# Power.net
KiCad netlist of a schematic drawn in Altium Designer
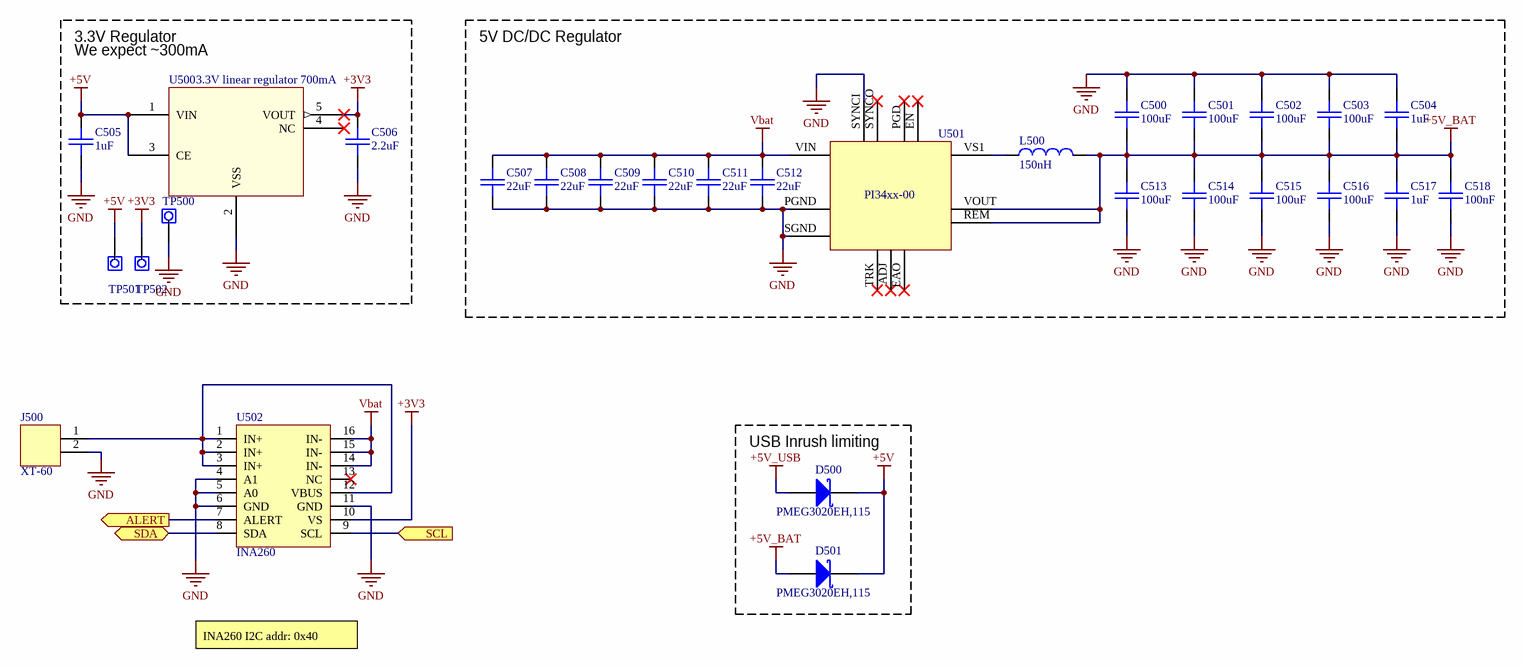
[diagram p0: Power.SchDoc]

(export (version "E")
  (design (tool "Eeschema 10.0.6"))
  (components
    (comp (ref "C500")
      (value "100uF")
      (footprint "1206_CAP")
      (libsource (lib "Moonlight-Components") (part "Capacitor"))
    )
    (comp (ref "C501")
      (value "100uF")
      (footprint "1206_CAP")
      (libsource (lib "Moonlight-Components") (part "Capacitor"))
    )
    (comp (ref "C502")
      (value "100uF")
      (footprint "1206_CAP")
      (libsource (lib "Moonlight-Components") (part "Capacitor"))
    )
    (comp (ref "C503")
      (value "100uF")
      (footprint "1206_CAP")
      (libsource (lib "Moonlight-Components") (part "Capacitor"))
    )
    (comp (ref "C504")
      (value "1uF")
      (footprint "0805_cap")
      (libsource (lib "Moonlight-Components") (part "Capacitor"))
    )
    (comp (ref "C505")
      (value "1uF")
      (footprint "0603_CAP")
      (libsource (lib "Moonlight_Components") (part "Capacitor"))
    )
    (comp (ref "C506")
      (value "2.2uF")
      (footprint "0603_CAP")
      (libsource (lib "Moonlight_Components") (part "Capacitor"))
    )
    (comp (ref "C507")
      (value "22uF")
      (footprint "1206_CAP")
      (libsource (lib "Moonlight-Components") (part "Capacitor"))
    )
    (comp (ref "C508")
      (value "22uF")
      (footprint "1206_CAP")
      (libsource (lib "Moonlight-Components") (part "Capacitor"))
    )
    (comp (ref "C509")
      (value "22uF")
      (footprint "1206_CAP")
      (libsource (lib "Moonlight-Components") (part "Capacitor"))
    )
    (comp (ref "C510")
      (value "22uF")
      (footprint "1206_CAP")
      (libsource (lib "Moonlight-Components") (part "Capacitor"))
    )
    (comp (ref "C511")
      (value "22uF")
      (footprint "1206_CAP")
      (libsource (lib "Moonlight-Components") (part "Capacitor"))
    )
    (comp (ref "C512")
      (value "22uF")
      (footprint "1206_CAP")
      (libsource (lib "Moonlight-Components") (part "Capacitor"))
    )
    (comp (ref "C513")
      (value "100uF")
      (footprint "1206_CAP")
      (libsource (lib "Moonlight-Components") (part "Capacitor"))
    )
    (comp (ref "C514")
      (value "100uF")
      (footprint "1206_CAP")
      (libsource (lib "Moonlight-Components") (part "Capacitor"))
    )
    (comp (ref "C515")
      (value "100uF")
      (footprint "1206_CAP")
      (libsource (lib "Moonlight-Components") (part "Capacitor"))
    )
    (comp (ref "C516")
      (value "100uF")
      (footprint "1206_CAP")
      (libsource (lib "Moonlight-Components") (part "Capacitor"))
    )
    (comp (ref "C517")
      (value "1uF")
      (footprint "0805_cap")
      (libsource (lib "Moonlight-Components") (part "Capacitor"))
    )
    (comp (ref "C518")
      (value "100nF")
      (footprint "1206_CAP")
      (libsource (lib "Moonlight-Components") (part "Capacitor"))
    )
    (comp (ref "D500")
      (value "PMEG3020EH,115")
      (footprint "SOD-123")
      (libsource (lib "Moonlight_Components") (part "Schottky diode"))
    )
    (comp (ref "D501")
      (value "PMEG3020EH,115")
      (footprint "SOD-123")
      (libsource (lib "Moonlight_Components") (part "Schottky diode"))
    )
    (comp (ref "J500")
      (value "XT-60")
      (footprint "XT-60")
      (description "Digikey part no. 1568-1816-ND")
      (libsource (lib "Moonlight-Components") (part "XT-60"))
    )
    (comp (ref "L500")
      (value "150nH")
      (footprint "FPV1006-150-R")
      (libsource (lib "Moonlight-Components") (part "Inductor"))
    )
    (comp (ref "TP500") (value "GND") (footprint "Testpoint2") (libsource (lib "") (part "Testpoint_1")))
    (comp (ref "TP501")
      (value "5V")
      (footprint "Testpoint2")
      (libsource (lib "Moonlight_Components") (part "Testpoint"))
    )
    (comp (ref "TP502")
      (value "3.3V")
      (footprint "Testpoint2")
      (libsource (lib "Moonlight_Components") (part "Testpoint"))
    )
    (comp (ref "U500")
      (value "3.3V linear regulator 700mA")
      (footprint "SOT-25_TOR")
      (description "Digikey part no. 893-1143-1-ND")
      (fields
        (field (name "MANUFACTURER_PART_NUMBER") "XC6222B331MR-G")
        (field (name "COPYRIGHT") "Copyright (C) 2018 Accelerated Designs. All rights reserved")
      )
      (libsource (lib "Moonlight_Components") (part "XC6222B331MR-G"))
    )
    (comp (ref "U501")
      (value "PI34xx-00")
      (footprint "PI34xx-00")
      (description "Digikey part no. 1102-1641-ND")
      (libsource (lib "Moonlight-Components") (part "PI34xx-00"))
    )
    (comp (ref "U502")
      (value "INA260")
      (footprint "TSSOP-16")
      (libsource (lib "Moonlight_Components") (part "INA260"))
    )
  )
  (nets
    (net (code "1") (name "+3V3") (class "Default")
      (node (ref "C506") (pin "1") (pinfunction "1_1") (pintype "passive"))
      (node (ref "TP502") (pin "1") (pinfunction "1_1") (pintype "passive"))
      (node (ref "U500") (pin "5") (pinfunction "VOUT_5") (pintype "output"))
      (node (ref "U502") (pin "10") (pinfunction "VS_10") (pintype "passive"))
    )
    (net (code "2") (name "+5V") (class "Default")
      (node (ref "C505") (pin "1") (pinfunction "1_1") (pintype "passive"))
      (node (ref "D500") (pin "2") (pinfunction "K_2") (pintype "passive"))
      (node (ref "D501") (pin "2") (pinfunction "K_2") (pintype "passive"))
      (node (ref "TP501") (pin "1") (pinfunction "1_1") (pintype "passive"))
      (node (ref "U500") (pin "1") (pinfunction "VIN_1") (pintype "power_in"))
      (node (ref "U500") (pin "3") (pinfunction "CE_3") (pintype "passive"))
    )
    (net (code "3") (name "+5V_BAT") (class "Default")
      (node (ref "C500") (pin "2") (pinfunction "2_2") (pintype "passive"))
      (node (ref "C501") (pin "2") (pinfunction "2_2") (pintype "passive"))
      (node (ref "C502") (pin "2") (pinfunction "2_2") (pintype "passive"))
      (node (ref "C503") (pin "2") (pinfunction "2_2") (pintype "passive"))
      (node (ref "C504") (pin "2") (pinfunction "2_2") (pintype "passive"))
      (node (ref "C513") (pin "1") (pinfunction "1_1") (pintype "passive"))
      (node (ref "C514") (pin "1") (pinfunction "1_1") (pintype "passive"))
      (node (ref "C515") (pin "1") (pinfunction "1_1") (pintype "passive"))
      (node (ref "C516") (pin "1") (pinfunction "1_1") (pintype "passive"))
      (node (ref "C517") (pin "1") (pinfunction "1_1") (pintype "passive"))
      (node (ref "C518") (pin "1") (pinfunction "1_1") (pintype "passive"))
      (node (ref "D501") (pin "1") (pinfunction "A_1") (pintype "passive"))
      (node (ref "L500") (pin "2") (pinfunction "2_2") (pintype "passive"))
      (node (ref "U501") (pin "REM") (pinfunction "REM_REM") (pintype "passive"))
      (node (ref "U501") (pin "VOUT") (pinfunction "VOUT_VOUT") (pintype "passive"))
    )
    (net (code "4") (name "+5V_USB") (class "Default")
      (node (ref "D500") (pin "1") (pinfunction "A_1") (pintype "passive"))
    )
    (net (code "5") (name "/ALERT") (class "Default")
      (node (ref "U502") (pin "7") (pinfunction "ALERT_7") (pintype "passive"))
    )
    (net (code "6") (name "/SCL") (class "Default")
      (node (ref "U502") (pin "9") (pinfunction "SCL_9") (pintype "passive"))
    )
    (net (code "7") (name "/SDA") (class "Default")
      (node (ref "U502") (pin "8") (pinfunction "SDA_8") (pintype "passive"))
    )
    (net (code "8") (name "GND") (class "Default")
      (node (ref "C500") (pin "1") (pinfunction "1_1") (pintype "passive"))
      (node (ref "C501") (pin "1") (pinfunction "1_1") (pintype "passive"))
      (node (ref "C502") (pin "1") (pinfunction "1_1") (pintype "passive"))
      (node (ref "C503") (pin "1") (pinfunction "1_1") (pintype "passive"))
      (node (ref "C504") (pin "1") (pinfunction "1_1") (pintype "passive"))
      (node (ref "C505") (pin "2") (pinfunction "2_2") (pintype "passive"))
      (node (ref "C506") (pin "2") (pinfunction "2_2") (pintype "passive"))
      (node (ref "C507") (pin "2") (pinfunction "2_2") (pintype "passive"))
      (node (ref "C508") (pin "2") (pinfunction "2_2") (pintype "passive"))
      (node (ref "C509") (pin "2") (pinfunction "2_2") (pintype "passive"))
      (node (ref "C510") (pin "2") (pinfunction "2_2") (pintype "passive"))
      (node (ref "C511") (pin "2") (pinfunction "2_2") (pintype "passive"))
      (node (ref "C512") (pin "2") (pinfunction "2_2") (pintype "passive"))
      (node (ref "C513") (pin "2") (pinfunction "2_2") (pintype "passive"))
      (node (ref "C514") (pin "2") (pinfunction "2_2") (pintype "passive"))
      (node (ref "C515") (pin "2") (pinfunction "2_2") (pintype "passive"))
      (node (ref "C516") (pin "2") (pinfunction "2_2") (pintype "passive"))
      (node (ref "C517") (pin "2") (pinfunction "2_2") (pintype "passive"))
      (node (ref "C518") (pin "2") (pinfunction "2_2") (pintype "passive"))
      (node (ref "J500") (pin "2") (pinfunction "2_2") (pintype "passive"))
      (node (ref "TP500") (pin "1") (pinfunction "1_1") (pintype "passive"))
      (node (ref "U500") (pin "2") (pinfunction "VSS_2") (pintype "passive"))
      (node (ref "U501") (pin "PGND") (pinfunction "PGND_PGND") (pintype "passive"))
      (node (ref "U501") (pin "SGND") (pinfunction "SGND_SGND") (pintype "passive"))
      (node (ref "U501") (pin "SYNCI") (pinfunction "SYNCI_SYNCI") (pintype "passive"))
      (node (ref "U502") (pin "11") (pinfunction "GND_11") (pintype "passive"))
      (node (ref "U502") (pin "4") (pinfunction "A1_4") (pintype "passive"))
      (node (ref "U502") (pin "5") (pinfunction "A0_5") (pintype "passive"))
      (node (ref "U502") (pin "6") (pinfunction "GND_6") (pintype "passive"))
    )
    (net (code "9") (name "Net-(L500-Pad1)") (class "Default")
      (node (ref "L500") (pin "1") (pinfunction "1_1") (pintype "passive"))
      (node (ref "U501") (pin "VS1") (pinfunction "VS1_VS1") (pintype "passive"))
    )
    (net (code "10") (name "Net-(U502-VBUS)") (class "Default")
      (node (ref "J500") (pin "1") (pinfunction "1_1") (pintype "passive"))
      (node (ref "U502") (pin "1") (pinfunction "IN+_1") (pintype "passive"))
      (node (ref "U502") (pin "12") (pinfunction "VBUS_12") (pintype "passive"))
      (node (ref "U502") (pin "2") (pinfunction "IN+_2") (pintype "passive"))
      (node (ref "U502") (pin "3") (pinfunction "IN+_3") (pintype "passive"))
    )
    (net (code "11") (name "Vbat") (class "Default")
      (node (ref "C507") (pin "1") (pinfunction "1_1") (pintype "passive"))
      (node (ref "C508") (pin "1") (pinfunction "1_1") (pintype "passive"))
      (node (ref "C509") (pin "1") (pinfunction "1_1") (pintype "passive"))
      (node (ref "C510") (pin "1") (pinfunction "1_1") (pintype "passive"))
      (node (ref "C511") (pin "1") (pinfunction "1_1") (pintype "passive"))
      (node (ref "C512") (pin "1") (pinfunction "1_1") (pintype "passive"))
      (node (ref "U501") (pin "VIN") (pinfunction "VIN_VIN") (pintype "passive"))
      (node (ref "U502") (pin "14") (pinfunction "IN-_14") (pintype "passive"))
      (node (ref "U502") (pin "15") (pinfunction "IN-_15") (pintype "passive"))
      (node (ref "U502") (pin "16") (pinfunction "IN-_16") (pintype "passive"))
    )
    (net (code "12") (name "unconnected-(U500-NC-Pad4)") (class "Default")
      (node (ref "U500") (pin "4") (pinfunction "NC_4") (pintype "passive+no_connect"))
    )
    (net (code "13") (name "unconnected-(U501-PadADJ)") (class "Default")
      (node (ref "U501") (pin "ADJ") (pinfunction "ADJ_ADJ") (pintype "passive+no_connect"))
    )
    (net (code "14") (name "unconnected-(U501-PadEAO)") (class "Default")
      (node (ref "U501") (pin "EAO") (pinfunction "EAO_EAO") (pintype "passive+no_connect"))
    )
    (net (code "15") (name "unconnected-(U501-PadEN)") (class "Default")
      (node (ref "U501") (pin "EN") (pinfunction "EN_EN") (pintype "passive+no_connect"))
    )
    (net (code "16") (name "unconnected-(U501-PadPGD)") (class "Default")
      (node (ref "U501") (pin "PGD") (pinfunction "PGD_PGD") (pintype "passive+no_connect"))
    )
    (net (code "17") (name "unconnected-(U501-PadSYNCO)") (class "Default")
      (node (ref "U501") (pin "SYNCO") (pinfunction "SYNCO_SYNCO") (pintype "passive+no_connect"))
    )
    (net (code "18") (name "unconnected-(U501-PadTRK)") (class "Default")
      (node (ref "U501") (pin "TRK") (pinfunction "TRK_TRK") (pintype "passive+no_connect"))
    )
    (net (code "19") (name "unconnected-(U502-NC-Pad13)") (class "Default")
      (node (ref "U502") (pin "13") (pinfunction "NC_13") (pintype "passive+no_connect"))
    )
  )
)
